# Sheet1.net
KiCad netlist of a schematic drawn in Altium Designer
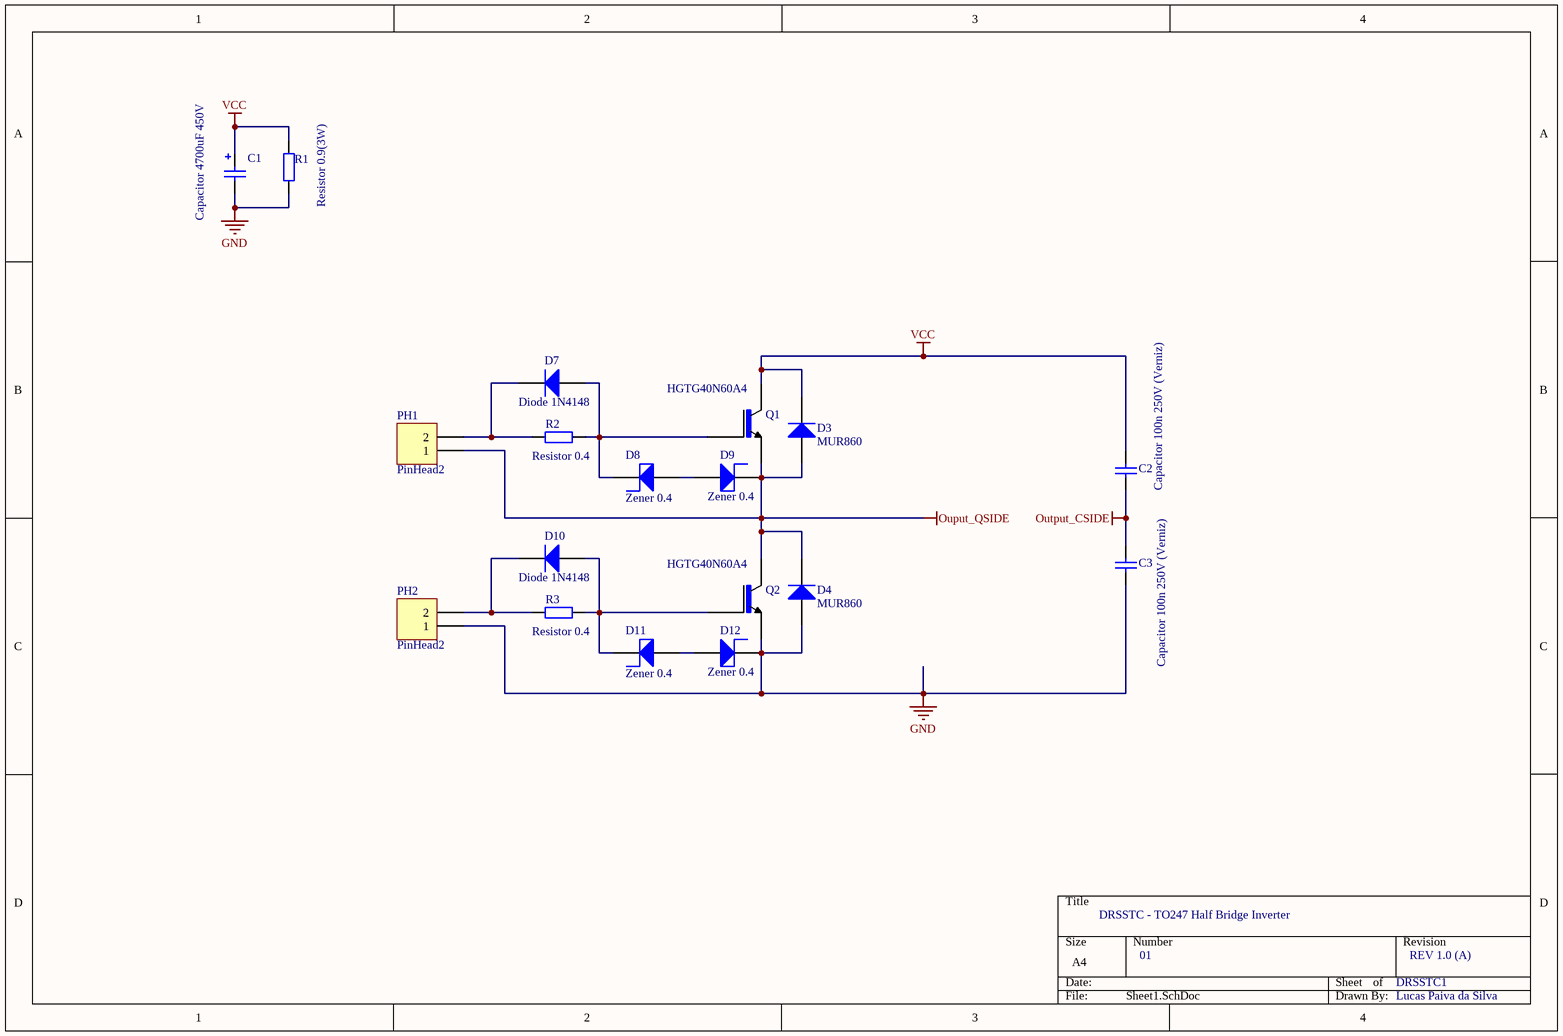
[diagram p0: Sheet1.SchDoc]

(export (version "E")
  (design (tool "Eeschema 10.0.6"))
  (components
    (comp (ref "C1")
      (value "Capacitor 4700uF 450V")
      (footprint "Capacitor 4700uF 450V RIFA")
      (libsource (lib "SPaivachlib1") (part "Capacitor 4700uF 450V"))
    )
    (comp (ref "C2")
      (value "Capacitor 100n 250V (Verniz)")
      (footprint "Capacitor 100n (cor verniz)")
      (libsource (lib "SPaivachlib1") (part "Capacitor 100n 250V (Verniz)"))
    )
    (comp (ref "C3")
      (value "Capacitor 100n 250V (Verniz)")
      (footprint "Capacitor 100n (cor verniz)")
      (libsource (lib "SPaivachlib1") (part "Capacitor 100n 250V (Verniz)"))
    )
    (comp (ref "D3") (value "MUR860") (footprint "MUR860") (libsource (lib "SPaivachlib1") (part "MUR860")))
    (comp (ref "D4") (value "MUR860") (footprint "MUR860") (libsource (lib "SPaivachlib1") (part "MUR860")))
    (comp (ref "D7")
      (value "Diode 1N4148")
      (footprint "Diode 8.89mm(350mils)")
      (libsource (lib "SPaivachlib1") (part "Diode 1N4148"))
    )
    (comp (ref "D8")
      (value "Zener 0.4")
      (footprint "Diode 0.4")
      (libsource (lib "SPaivachlib1") (part "Zener 0.4"))
    )
    (comp (ref "D9")
      (value "Zener 0.4")
      (footprint "Diode 0.4")
      (libsource (lib "SPaivachlib1") (part "Zener 0.4"))
    )
    (comp (ref "D10")
      (value "Diode 1N4148")
      (footprint "Diode 8.89mm(350mils)")
      (libsource (lib "SPaivachlib1") (part "Diode 1N4148"))
    )
    (comp (ref "D11")
      (value "Zener 0.4")
      (footprint "Diode 0.4")
      (libsource (lib "SPaivachlib1") (part "Zener 0.4"))
    )
    (comp (ref "D12")
      (value "Zener 0.4")
      (footprint "Diode 0.4")
      (libsource (lib "SPaivachlib1") (part "Zener 0.4"))
    )
    (comp (ref "PH1")
      (value "PinHead2")
      (footprint "PinHead2")
      (libsource (lib "SPaivachlib1") (part "PinHead2"))
    )
    (comp (ref "PH2")
      (value "PinHead2")
      (footprint "PinHead2")
      (libsource (lib "SPaivachlib1") (part "PinHead2"))
    )
    (comp (ref "Q1")
      (value "HGTG40N60A4")
      (footprint "HGTG40N60A4")
      (libsource (lib "SPaivachlib1") (part "HGTG40N60A4"))
    )
    (comp (ref "Q2")
      (value "HGTG40N60A4")
      (footprint "HGTG40N60A4")
      (libsource (lib "SPaivachlib1") (part "HGTG40N60A4"))
    )
    (comp (ref "R1")
      (value "Resistor 0.9(3W)")
      (footprint "Resistor Axial 0.9(3W)")
      (libsource (lib "SPaivachlib1") (part "Resistor 0.9(3W)"))
    )
    (comp (ref "R2")
      (value "Resistor 0.4")
      (footprint "Resistor Axial 0.4")
      (libsource (lib "SPaivachlib1") (part "Resistor 0.4"))
    )
    (comp (ref "R3")
      (value "Resistor 0.4")
      (footprint "Resistor Axial 0.4")
      (libsource (lib "SPaivachlib1") (part "Resistor 0.4"))
    )
  )
  (nets
    (net (code "1") (name "GND") (class "Default")
      (node (ref "C1") (pin "1") (pinfunction "1_1") (pintype "passive"))
      (node (ref "C3") (pin "1") (pinfunction "1_1") (pintype "passive"))
      (node (ref "D12") (pin "K") (pinfunction "K_K") (pintype "passive"))
      (node (ref "D4") (pin "3") (pinfunction "A_3") (pintype "passive"))
      (node (ref "PH2") (pin "1") (pinfunction "1_1") (pintype "passive"))
      (node (ref "Q2") (pin "3") (pinfunction "E_3") (pintype "passive"))
      (node (ref "R1") (pin "1") (pinfunction "1_1") (pintype "passive"))
    )
    (net (code "2") (name "Net-(D7-PadK)") (class "Default")
      (node (ref "D7") (pin "K") (pinfunction "K_K") (pintype "passive"))
      (node (ref "PH1") (pin "2") (pinfunction "2_2") (pintype "passive"))
      (node (ref "R2") (pin "1") (pinfunction "1_1") (pintype "passive"))
    )
    (net (code "3") (name "Net-(D8-PadA)") (class "Default")
      (node (ref "D8") (pin "A") (pinfunction "A_A") (pintype "passive"))
      (node (ref "D9") (pin "A") (pinfunction "A_A") (pintype "passive"))
    )
    (net (code "4") (name "Net-(D10-PadK)") (class "Default")
      (node (ref "D10") (pin "K") (pinfunction "K_K") (pintype "passive"))
      (node (ref "PH2") (pin "2") (pinfunction "2_2") (pintype "passive"))
      (node (ref "R3") (pin "1") (pinfunction "1_1") (pintype "passive"))
    )
    (net (code "5") (name "Net-(D11-PadA)") (class "Default")
      (node (ref "D11") (pin "A") (pinfunction "A_A") (pintype "passive"))
      (node (ref "D12") (pin "A") (pinfunction "A_A") (pintype "passive"))
    )
    (net (code "6") (name "Net-(Q1-G)") (class "Default")
      (node (ref "D7") (pin "A") (pinfunction "A_A") (pintype "passive"))
      (node (ref "D8") (pin "K") (pinfunction "K_K") (pintype "passive"))
      (node (ref "Q1") (pin "1") (pinfunction "G_1") (pintype "passive"))
      (node (ref "R2") (pin "2") (pinfunction "2_2") (pintype "passive"))
    )
    (net (code "7") (name "Net-(Q2-G)") (class "Default")
      (node (ref "D10") (pin "A") (pinfunction "A_A") (pintype "passive"))
      (node (ref "D11") (pin "K") (pinfunction "K_K") (pintype "passive"))
      (node (ref "Q2") (pin "1") (pinfunction "G_1") (pintype "passive"))
      (node (ref "R3") (pin "2") (pinfunction "2_2") (pintype "passive"))
    )
    (net (code "8") (name "Ouput_QSIDE") (class "Default")
      (node (ref "D3") (pin "3") (pinfunction "A_3") (pintype "passive"))
      (node (ref "D4") (pin "1") (pinfunction "K_1") (pintype "passive"))
      (node (ref "D9") (pin "K") (pinfunction "K_K") (pintype "passive"))
      (node (ref "PH1") (pin "1") (pinfunction "1_1") (pintype "passive"))
      (node (ref "Q1") (pin "3") (pinfunction "E_3") (pintype "passive"))
      (node (ref "Q2") (pin "2") (pinfunction "C_2") (pintype "passive"))
    )
    (net (code "9") (name "Output_CSIDE") (class "Default")
      (node (ref "C2") (pin "1") (pinfunction "1_1") (pintype "passive"))
      (node (ref "C3") (pin "2") (pinfunction "2_2") (pintype "passive"))
    )
    (net (code "10") (name "VCC") (class "Default")
      (node (ref "C1") (pin "2") (pinfunction "2_2") (pintype "passive"))
      (node (ref "C2") (pin "2") (pinfunction "2_2") (pintype "passive"))
      (node (ref "D3") (pin "1") (pinfunction "K_1") (pintype "passive"))
      (node (ref "Q1") (pin "2") (pinfunction "C_2") (pintype "passive"))
      (node (ref "R1") (pin "2") (pinfunction "2_2") (pintype "passive"))
    )
  )
)
